# ESP32-C3-Devkit-M1.net
KiCad netlist of a schematic drawn in EasyEDA Pro
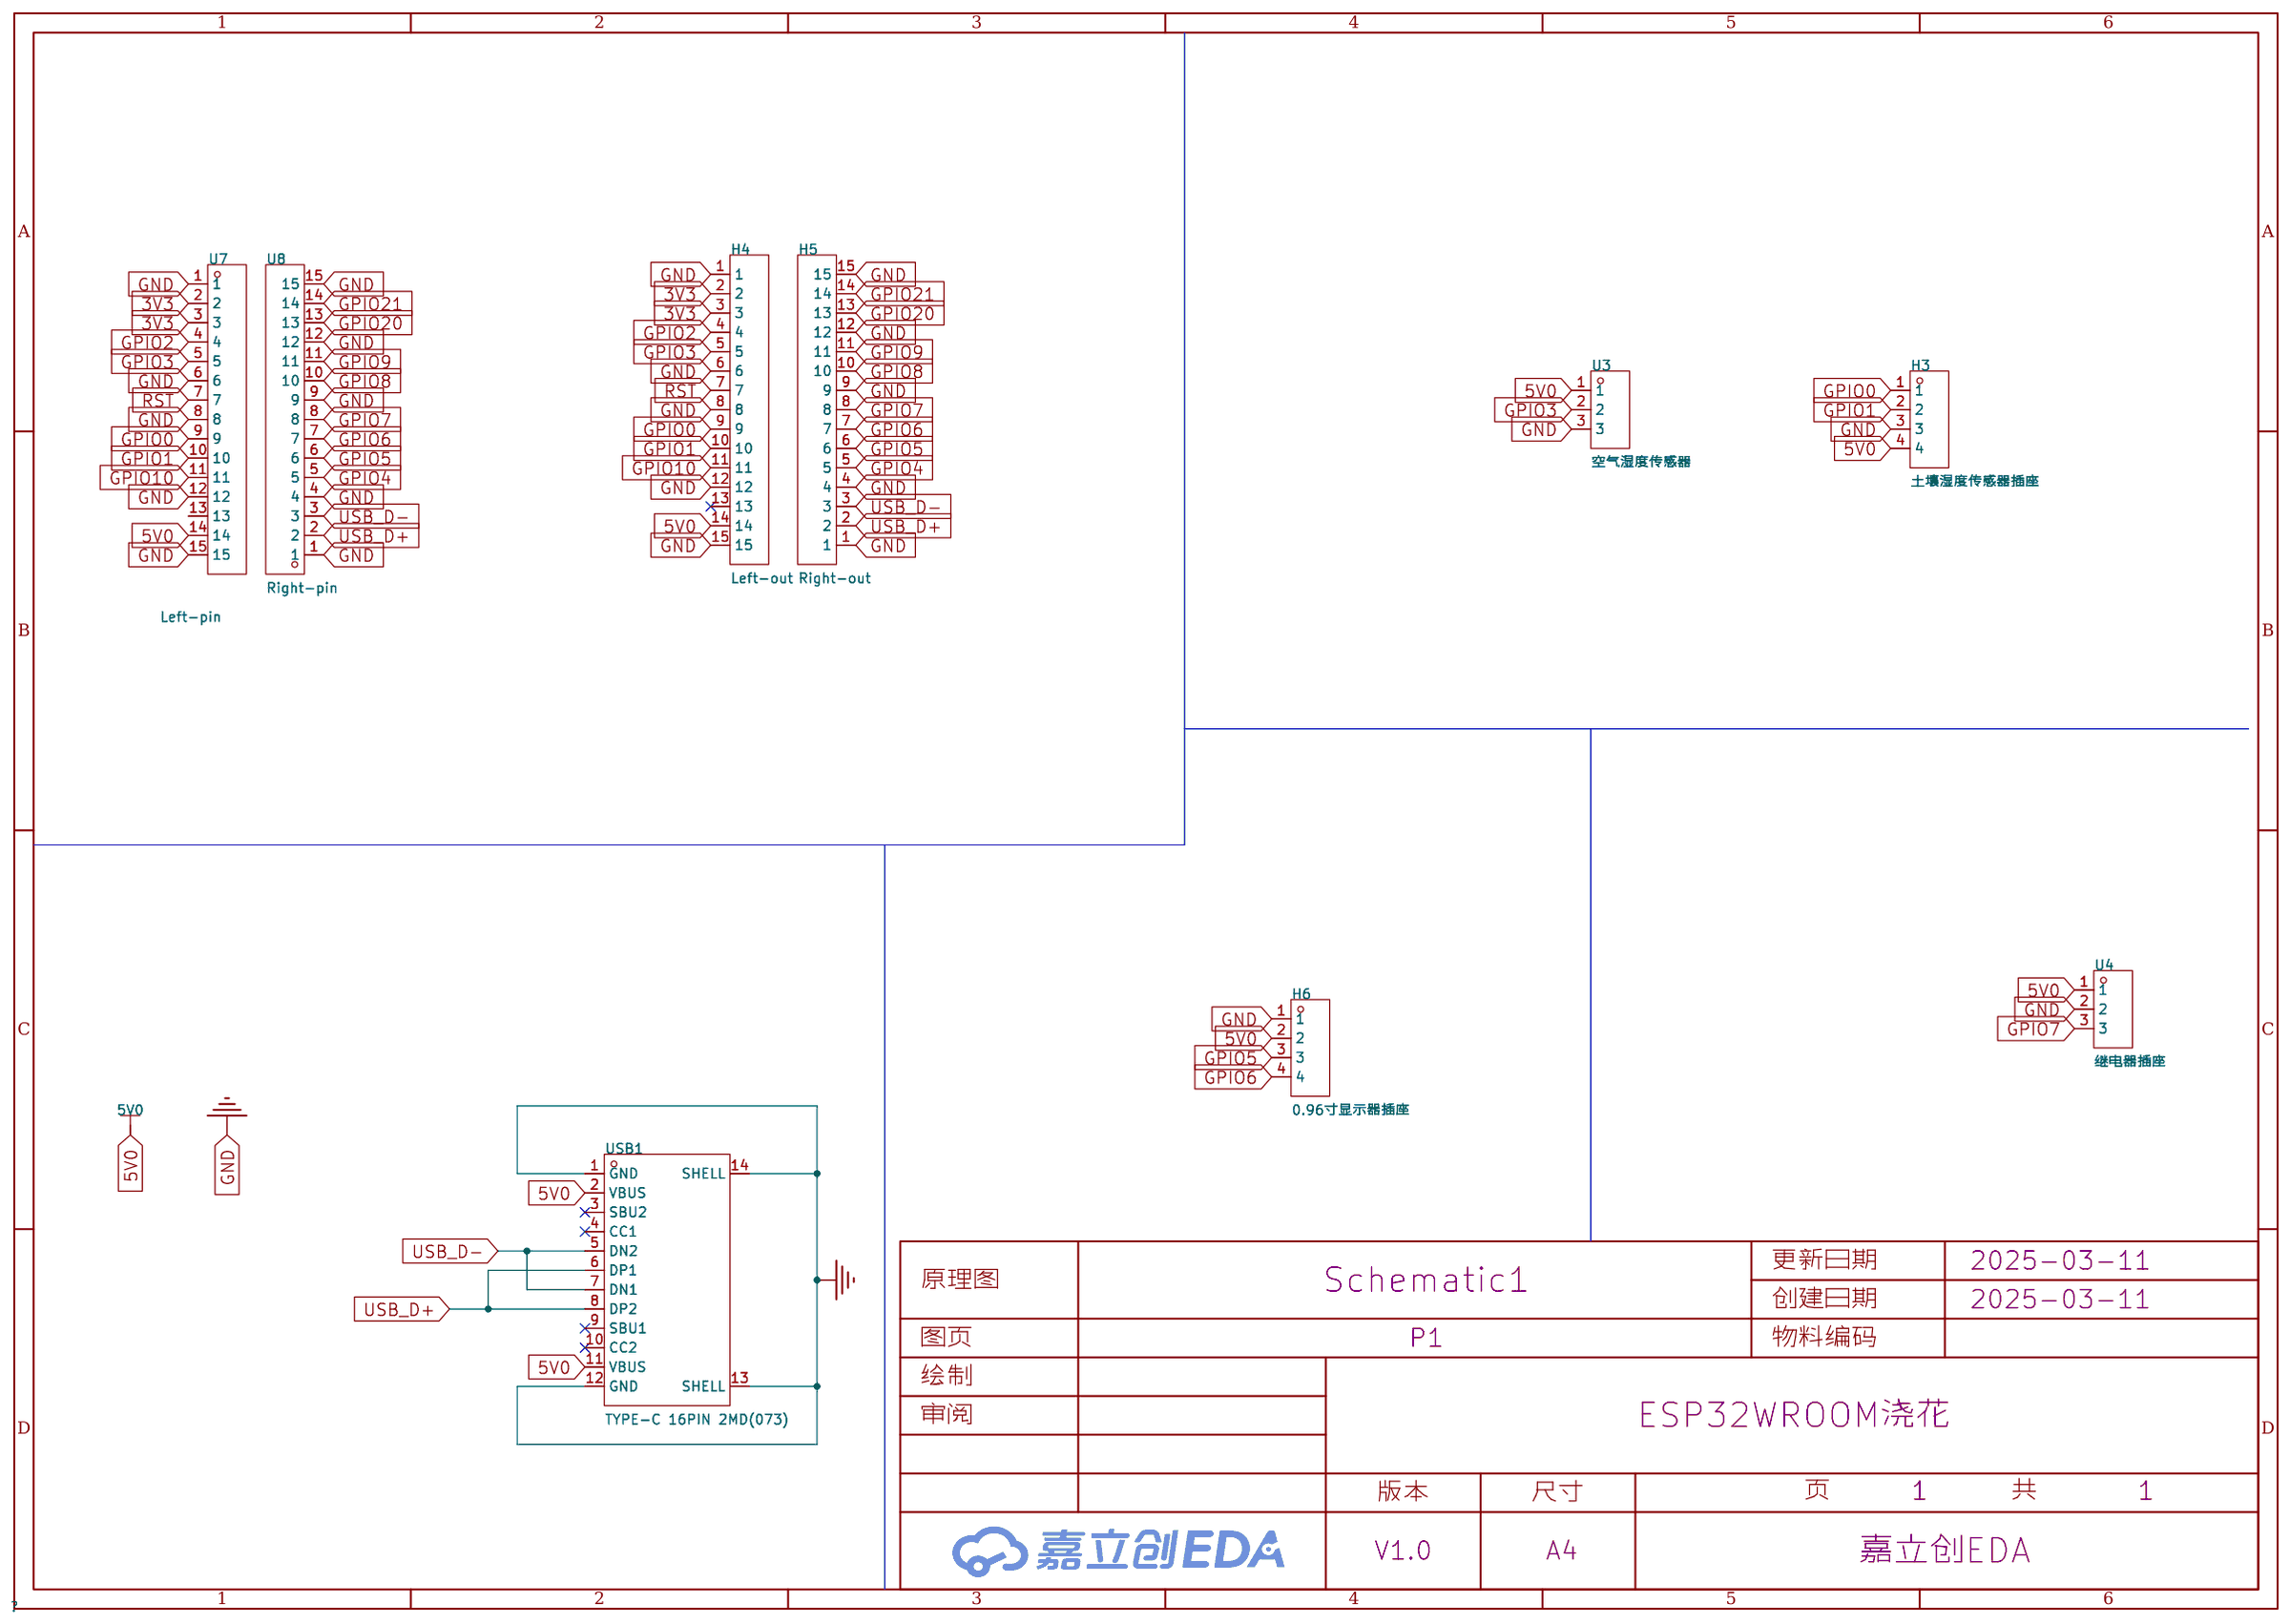
[diagram p0: schematic sheet]

(export (version "E")
  (design (tool "Eeschema 10.0.6"))
  (components
    (comp (ref "H3")
      (value "土壤湿度传感器插座")
      (footprint "easyedapro:HDR-TH_4P-P2.54-V-F")
      (fields (field (name "Manufacturer") "BOOMELE(博穆精密)"))
      (libsource (lib "easyedapro") (part "2.54-1*4P母"))
    )
    (comp (ref "H4")
      (value "Left-out")
      (footprint "easyedapro:HDR-TH_15P-P2.54-V-M")
      (fields (field (name "Manufacturer") "kinghelm(金航标)"))
      (libsource (lib "easyedapro") (part "KH-2.54PH180-1X15P-L11.5"))
    )
    (comp (ref "H5")
      (value "Right-out")
      (footprint "easyedapro:HDR-TH_15P-P2.54-V-M")
      (fields (field (name "Manufacturer") "kinghelm(金航标)"))
      (libsource (lib "easyedapro") (part "KH-2.54PH180-1X15P-L11.5"))
    )
    (comp (ref "H6")
      (value "0.96寸显示器插座")
      (footprint "easyedapro:HDR-TH_4P-P2.54-V-F")
      (fields (field (name "Manufacturer") "BOOMELE(博穆精密)"))
      (libsource (lib "easyedapro") (part "2.54-1*4P母"))
    )
    (comp (ref "U3")
      (value "空气湿度传感器")
      (footprint "easyedapro:HDR-TH_3P-P2.54_CS-1165SDIG")
      (libsource (lib "easyedapro") (part "排母2.54MM 1X3PIN"))
    )
    (comp (ref "U4")
      (value "继电器插座")
      (footprint "easyedapro:HDR-TH_3P-P2.54_CS-1165SDIG")
      (libsource (lib "easyedapro") (part "排母2.54MM 1X3PIN"))
    )
    (comp (ref "U7")
      (value "Left-pin")
      (footprint "easyedapro:HDR-TH_15P-P2.54-V-F")
      (fields (field (name "Manufacturer") "HC(虹成电子)"))
      (libsource (lib "easyedapro") (part "HC-PM254-8.5H-1X15PZ"))
    )
    (comp (ref "U8")
      (value "Right-pin")
      (footprint "easyedapro:HDR-TH_15P-P2.54-V-F")
      (fields (field (name "Manufacturer") "HC(虹成电子)"))
      (libsource (lib "easyedapro") (part "HC-PM254-8.5H-1X15PZ"))
    )
    (comp (ref "USB1")
      (value "TYPE-C 16PIN 2MD(073)")
      (footprint "easyedapro:USB-C-SMD_TYPE-C-6PIN-2MD-073")
      (description "连接器类型:Type-C;标准:USB 3.1;公母:母;安装方式:卧贴;触点数量:16P;端口数量:1;额定电流 - 电源:5A;工作温度范围:-25°C~+85°C;")
      (fields (field (name "Manufacturer") "SHOU HAN(首韩)"))
      (libsource (lib "easyedapro") (part "TYPE-C 16PIN 2MD(073)"))
    )
  )
  (nets
    (net (code "1") (name "3V3") (class "Default")
      (node (ref "H4") (pin "2") (pinfunction "2_2") (pintype "unspecified"))
      (node (ref "H4") (pin "3") (pinfunction "3_3") (pintype "unspecified"))
      (node (ref "U7") (pin "2") (pinfunction "2_2") (pintype "unspecified"))
      (node (ref "U7") (pin "3") (pinfunction "3_3") (pintype "unspecified"))
    )
    (net (code "2") (name "5V0") (class "Default")
      (node (ref "H3") (pin "4") (pinfunction "4_4") (pintype "unspecified"))
      (node (ref "H4") (pin "14") (pinfunction "14_14") (pintype "unspecified"))
      (node (ref "H6") (pin "2") (pinfunction "2_2") (pintype "unspecified"))
      (node (ref "U3") (pin "1") (pinfunction "1_1") (pintype "unspecified"))
      (node (ref "U4") (pin "1") (pinfunction "1_1") (pintype "unspecified"))
      (node (ref "U7") (pin "14") (pinfunction "14_14") (pintype "unspecified"))
      (node (ref "USB1") (pin "11") (pinfunction "VBUS_11") (pintype "unspecified"))
      (node (ref "USB1") (pin "2") (pinfunction "VBUS_2") (pintype "unspecified"))
    )
    (net (code "3") (name "GND") (class "Default")
      (node (ref "H3") (pin "3") (pinfunction "3_3") (pintype "unspecified"))
      (node (ref "H4") (pin "1") (pinfunction "1_1") (pintype "unspecified"))
      (node (ref "H4") (pin "12") (pinfunction "12_12") (pintype "unspecified"))
      (node (ref "H4") (pin "15") (pinfunction "15_15") (pintype "unspecified"))
      (node (ref "H4") (pin "6") (pinfunction "6_6") (pintype "unspecified"))
      (node (ref "H4") (pin "8") (pinfunction "8_8") (pintype "unspecified"))
      (node (ref "H5") (pin "1") (pinfunction "1_1") (pintype "unspecified"))
      (node (ref "H5") (pin "12") (pinfunction "12_12") (pintype "unspecified"))
      (node (ref "H5") (pin "15") (pinfunction "15_15") (pintype "unspecified"))
      (node (ref "H5") (pin "4") (pinfunction "4_4") (pintype "unspecified"))
      (node (ref "H5") (pin "9") (pinfunction "9_9") (pintype "unspecified"))
      (node (ref "H6") (pin "1") (pinfunction "1_1") (pintype "unspecified"))
      (node (ref "U3") (pin "3") (pinfunction "3_3") (pintype "unspecified"))
      (node (ref "U4") (pin "2") (pinfunction "2_2") (pintype "unspecified"))
      (node (ref "U7") (pin "1") (pinfunction "1_1") (pintype "unspecified"))
      (node (ref "U7") (pin "12") (pinfunction "12_12") (pintype "unspecified"))
      (node (ref "U7") (pin "15") (pinfunction "15_15") (pintype "unspecified"))
      (node (ref "U7") (pin "6") (pinfunction "6_6") (pintype "unspecified"))
      (node (ref "U7") (pin "8") (pinfunction "8_8") (pintype "unspecified"))
      (node (ref "U8") (pin "1") (pinfunction "1_1") (pintype "unspecified"))
      (node (ref "U8") (pin "12") (pinfunction "12_12") (pintype "unspecified"))
      (node (ref "U8") (pin "15") (pinfunction "15_15") (pintype "unspecified"))
      (node (ref "U8") (pin "4") (pinfunction "4_4") (pintype "unspecified"))
      (node (ref "U8") (pin "9") (pinfunction "9_9") (pintype "unspecified"))
      (node (ref "USB1") (pin "1") (pinfunction "GND_1") (pintype "unspecified"))
      (node (ref "USB1") (pin "12") (pinfunction "GND_12") (pintype "unspecified"))
      (node (ref "USB1") (pin "13") (pinfunction "SHELL_13") (pintype "unspecified"))
      (node (ref "USB1") (pin "14") (pinfunction "SHELL_14") (pintype "unspecified"))
    )
    (net (code "4") (name "GPIO0") (class "Default")
      (node (ref "H3") (pin "1") (pinfunction "1_1") (pintype "unspecified"))
      (node (ref "H4") (pin "9") (pinfunction "9_9") (pintype "unspecified"))
      (node (ref "U7") (pin "9") (pinfunction "9_9") (pintype "unspecified"))
    )
    (net (code "5") (name "GPIO1") (class "Default")
      (node (ref "H3") (pin "2") (pinfunction "2_2") (pintype "unspecified"))
      (node (ref "H4") (pin "10") (pinfunction "10_10") (pintype "unspecified"))
      (node (ref "U7") (pin "10") (pinfunction "10_10") (pintype "unspecified"))
    )
    (net (code "6") (name "GPIO2") (class "Default")
      (node (ref "H4") (pin "4") (pinfunction "4_4") (pintype "unspecified"))
      (node (ref "U7") (pin "4") (pinfunction "4_4") (pintype "unspecified"))
    )
    (net (code "7") (name "GPIO3") (class "Default")
      (node (ref "H4") (pin "5") (pinfunction "5_5") (pintype "unspecified"))
      (node (ref "U3") (pin "2") (pinfunction "2_2") (pintype "unspecified"))
      (node (ref "U7") (pin "5") (pinfunction "5_5") (pintype "unspecified"))
    )
    (net (code "8") (name "GPIO4") (class "Default")
      (node (ref "H5") (pin "5") (pinfunction "5_5") (pintype "unspecified"))
      (node (ref "U8") (pin "5") (pinfunction "5_5") (pintype "unspecified"))
    )
    (net (code "9") (name "GPIO5") (class "Default")
      (node (ref "H5") (pin "6") (pinfunction "6_6") (pintype "unspecified"))
      (node (ref "H6") (pin "3") (pinfunction "3_3") (pintype "unspecified"))
      (node (ref "U8") (pin "6") (pinfunction "6_6") (pintype "unspecified"))
    )
    (net (code "10") (name "GPIO6") (class "Default")
      (node (ref "H5") (pin "7") (pinfunction "7_7") (pintype "unspecified"))
      (node (ref "H6") (pin "4") (pinfunction "4_4") (pintype "unspecified"))
      (node (ref "U8") (pin "7") (pinfunction "7_7") (pintype "unspecified"))
    )
    (net (code "11") (name "GPIO7") (class "Default")
      (node (ref "H5") (pin "8") (pinfunction "8_8") (pintype "unspecified"))
      (node (ref "U4") (pin "3") (pinfunction "3_3") (pintype "unspecified"))
      (node (ref "U8") (pin "8") (pinfunction "8_8") (pintype "unspecified"))
    )
    (net (code "12") (name "GPIO8") (class "Default")
      (node (ref "H5") (pin "10") (pinfunction "10_10") (pintype "unspecified"))
      (node (ref "U8") (pin "10") (pinfunction "10_10") (pintype "unspecified"))
    )
    (net (code "13") (name "GPIO9") (class "Default")
      (node (ref "H5") (pin "11") (pinfunction "11_11") (pintype "unspecified"))
      (node (ref "U8") (pin "11") (pinfunction "11_11") (pintype "unspecified"))
    )
    (net (code "14") (name "GPIO10") (class "Default")
      (node (ref "H4") (pin "11") (pinfunction "11_11") (pintype "unspecified"))
      (node (ref "U7") (pin "11") (pinfunction "11_11") (pintype "unspecified"))
    )
    (net (code "15") (name "GPIO20") (class "Default")
      (node (ref "H5") (pin "13") (pinfunction "13_13") (pintype "unspecified"))
      (node (ref "U8") (pin "13") (pinfunction "13_13") (pintype "unspecified"))
    )
    (net (code "16") (name "GPIO21") (class "Default")
      (node (ref "H5") (pin "14") (pinfunction "14_14") (pintype "unspecified"))
      (node (ref "U8") (pin "14") (pinfunction "14_14") (pintype "unspecified"))
    )
    (net (code "17") (name "RST") (class "Default")
      (node (ref "H4") (pin "7") (pinfunction "7_7") (pintype "unspecified"))
      (node (ref "U7") (pin "7") (pinfunction "7_7") (pintype "unspecified"))
    )
    (net (code "18") (name "USB_D+") (class "Default")
      (node (ref "H5") (pin "2") (pinfunction "2_2") (pintype "unspecified"))
      (node (ref "U8") (pin "2") (pinfunction "2_2") (pintype "unspecified"))
      (node (ref "USB1") (pin "6") (pinfunction "DP1_6") (pintype "unspecified"))
      (node (ref "USB1") (pin "8") (pinfunction "DP2_8") (pintype "unspecified"))
    )
    (net (code "19") (name "USB_D-") (class "Default")
      (node (ref "H5") (pin "3") (pinfunction "3_3") (pintype "unspecified"))
      (node (ref "U8") (pin "3") (pinfunction "3_3") (pintype "unspecified"))
      (node (ref "USB1") (pin "5") (pinfunction "DN2_5") (pintype "unspecified"))
      (node (ref "USB1") (pin "7") (pinfunction "DN1_7") (pintype "unspecified"))
    )
    (net (code "20") (name "unconnected-(H4-Pad13)") (class "Default")
      (node (ref "H4") (pin "13") (pinfunction "13_13") (pintype "unspecified+no_connect"))
    )
    (net (code "21") (name "unconnected-(U7-Pad13)") (class "Default")
      (node (ref "U7") (pin "13") (pinfunction "13_13") (pintype "unspecified"))
    )
    (net (code "22") (name "unconnected-(USB1-CC1-Pad4)") (class "Default")
      (node (ref "USB1") (pin "4") (pinfunction "CC1_4") (pintype "unspecified+no_connect"))
    )
    (net (code "23") (name "unconnected-(USB1-CC2-Pad10)") (class "Default")
      (node (ref "USB1") (pin "10") (pinfunction "CC2_10") (pintype "unspecified+no_connect"))
    )
    (net (code "24") (name "unconnected-(USB1-SBU1-Pad9)") (class "Default")
      (node (ref "USB1") (pin "9") (pinfunction "SBU1_9") (pintype "unspecified+no_connect"))
    )
    (net (code "25") (name "unconnected-(USB1-SBU2-Pad3)") (class "Default")
      (node (ref "USB1") (pin "3") (pinfunction "SBU2_3") (pintype "unspecified+no_connect"))
    )
  )
)
